# rcontrol.net
KiCad netlist of a schematic drawn in EAGLE
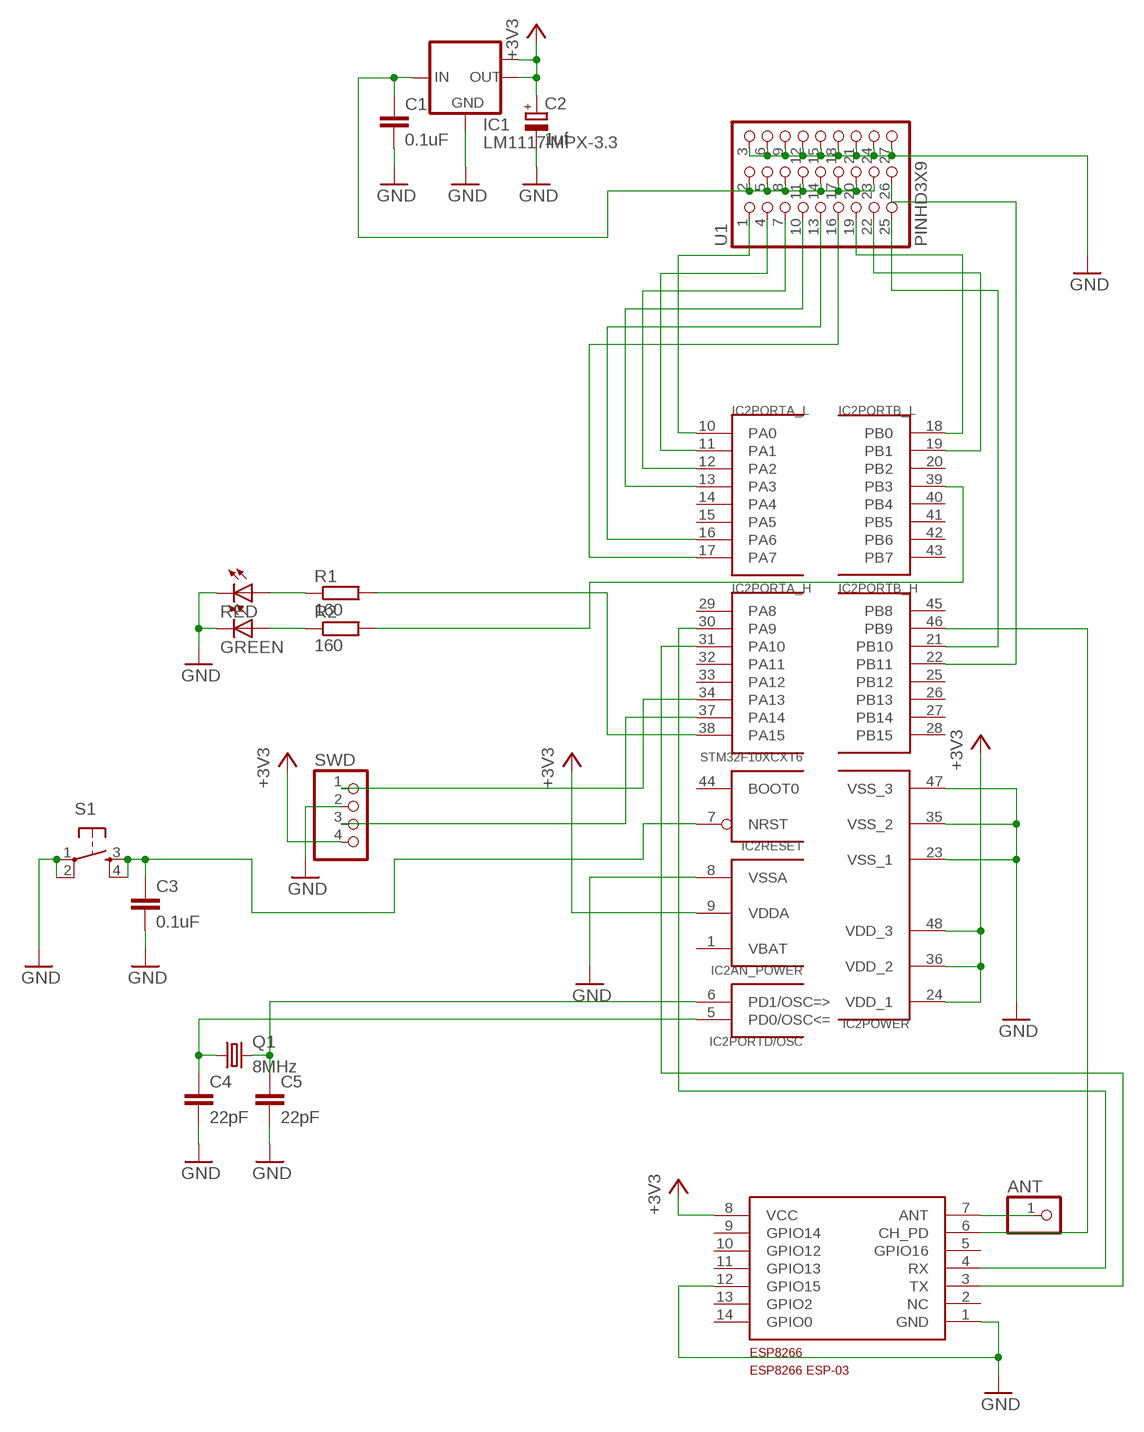
[diagram p0: schematic, sheet 1]

(export (version "E")
  (design (tool "Eeschema 10.0.6"))
  (components
    (comp (ref "ANT")
      (value "PINHD-1X1")
      (footprint "eagle-import:1X01")
      (libsource (lib "eagle-import") (part "PINHD-1X1"))
    )
    (comp (ref "C1")
      (value "0.1uF")
      (footprint "eagle-import:C1206")
      (libsource (lib "eagle-import") (part "C-EUC1206"))
    )
    (comp (ref "C2")
      (value "1uf")
      (footprint "eagle-import:CT3528")
      (libsource (lib "eagle-import") (part "CPOL-EUCT3528"))
    )
    (comp (ref "C3")
      (value "0.1uF")
      (footprint "eagle-import:C0805")
      (libsource (lib "eagle-import") (part "C-EUC0805"))
    )
    (comp (ref "C4")
      (value "22pF")
      (footprint "eagle-import:C0805")
      (libsource (lib "eagle-import") (part "C-EUC0805"))
    )
    (comp (ref "C5")
      (value "22pF")
      (footprint "eagle-import:C0805")
      (libsource (lib "eagle-import") (part "C-EUC0805"))
    )
    (comp (ref "ESP8266")
      (value "ESP8266_ESP-03")
      (footprint "eagle-import:ESP-03")
      (libsource (lib "eagle-import") (part "ESP8266_ESP-03"))
    )
    (comp (ref "GREEN")
      (value "LEDCHIP-LED0805")
      (footprint "eagle-import:CHIP-LED0805")
      (libsource (lib "eagle-import") (part "LEDCHIP-LED0805"))
    )
    (comp (ref "IC1")
      (value "LM1117IMPX-3.3")
      (footprint "eagle-import:SOT223")
      (libsource (lib "eagle-import") (part "LM1117IMPX-3.3"))
    )
    (comp (ref "IC2")
      (value "STM32F10XCXT6")
      (footprint "eagle-import:TQFP48")
      (libsource (lib "eagle-import") (part "STM32F10XCXT6"))
    )
    (comp (ref "Q1")
      (value "8MHz")
      (footprint "eagle-import:HC49U-V")
      (libsource (lib "eagle-import") (part "CRYSTALHC49U-V"))
    )
    (comp (ref "R1")
      (value "160")
      (footprint "eagle-import:R0805")
      (libsource (lib "eagle-import") (part "R-EU_R0805"))
    )
    (comp (ref "R2")
      (value "160")
      (footprint "eagle-import:R0805")
      (libsource (lib "eagle-import") (part "R-EU_R0805"))
    )
    (comp (ref "RED")
      (value "LEDCHIP-LED0805")
      (footprint "eagle-import:CHIP-LED0805")
      (libsource (lib "eagle-import") (part "LEDCHIP-LED0805"))
    )
    (comp (ref "S1")
      (value "TAC_SWITCHSMD")
      (footprint "eagle-import:TACTILE_SWITCH_SMD")
      (libsource (lib "eagle-import") (part "TAC_SWITCHSMD"))
    )
    (comp (ref "SWD")
      (value "PINHD-1X4")
      (footprint "eagle-import:1X04")
      (libsource (lib "eagle-import") (part "PINHD-1X4"))
    )
    (comp (ref "U1")
      (value "PINHD3X9")
      (footprint "eagle-import:3X9")
      (libsource (lib "eagle-import") (part "PINHD3X9"))
    )
  )
  (nets
    (net (code "1") (name "+3V3") (class "Default")
      (node (ref "C2") (pin "+") (pinfunction "+_+") (pintype "passive"))
      (node (ref "ESP8266") (pin "8") (pinfunction "VCC_8") (pintype "bidirectional"))
      (node (ref "IC1") (pin "2") (pinfunction "OUT_2") (pintype "passive"))
      (node (ref "IC1") (pin "TAB") (pinfunction "OUT1_TAB") (pintype "passive"))
      (node (ref "IC2") (pin "24") (pinfunction "VDD_1_24") (pintype "power_in"))
      (node (ref "IC2") (pin "36") (pinfunction "VDD_2_36") (pintype "power_in"))
      (node (ref "IC2") (pin "48") (pinfunction "VDD_3_48") (pintype "power_in"))
      (node (ref "IC2") (pin "9") (pinfunction "VDDA_9") (pintype "power_in"))
      (node (ref "SWD") (pin "4") (pinfunction "4_4") (pintype "passive"))
    )
    (net (code "2") (name "/VBAT") (class "Default")
      (node (ref "IC2") (pin "1") (pinfunction "VBAT_1") (pintype "power_in"))
    )
    (net (code "3") (name "GND") (class "Default")
      (node (ref "C1") (pin "2") (pinfunction "2_2") (pintype "passive"))
      (node (ref "C2") (pin "-") (pinfunction "-_-") (pintype "passive"))
      (node (ref "C3") (pin "2") (pinfunction "2_2") (pintype "passive"))
      (node (ref "C4") (pin "2") (pinfunction "2_2") (pintype "passive"))
      (node (ref "C5") (pin "2") (pinfunction "2_2") (pintype "passive"))
      (node (ref "ESP8266") (pin "1") (pinfunction "GND_1") (pintype "bidirectional"))
      (node (ref "ESP8266") (pin "12") (pinfunction "GPIO15_12") (pintype "bidirectional"))
      (node (ref "GREEN") (pin "C") (pinfunction "C_C") (pintype "passive"))
      (node (ref "IC1") (pin "1") (pinfunction "GND_1") (pintype "input"))
      (node (ref "IC2") (pin "23") (pinfunction "VSS_1_23") (pintype "power_in"))
      (node (ref "IC2") (pin "35") (pinfunction "VSS_2_35") (pintype "power_in"))
      (node (ref "IC2") (pin "47") (pinfunction "VSS_3_47") (pintype "power_in"))
      (node (ref "IC2") (pin "8") (pinfunction "VSSA_8") (pintype "power_in"))
      (node (ref "RED") (pin "C") (pinfunction "C_C") (pintype "passive"))
      (node (ref "S1") (pin "1") (pinfunction "1_1") (pintype "passive"))
      (node (ref "S1") (pin "2") (pinfunction "2_2") (pintype "passive"))
      (node (ref "SWD") (pin "2") (pinfunction "2_2") (pintype "passive"))
      (node (ref "U1") (pin "12") (pinfunction "12_12") (pintype "passive"))
      (node (ref "U1") (pin "15") (pinfunction "15_15") (pintype "passive"))
      (node (ref "U1") (pin "18") (pinfunction "18_18") (pintype "passive"))
      (node (ref "U1") (pin "21") (pinfunction "21_21") (pintype "passive"))
      (node (ref "U1") (pin "24") (pinfunction "24_24") (pintype "passive"))
      (node (ref "U1") (pin "27") (pinfunction "27_27") (pintype "passive"))
      (node (ref "U1") (pin "3") (pinfunction "3_3") (pintype "passive"))
      (node (ref "U1") (pin "6") (pinfunction "6_6") (pintype "passive"))
      (node (ref "U1") (pin "9") (pinfunction "9_9") (pintype "passive"))
    )
    (net (code "4") (name "Net-(ESP8266-ANT)") (class "Default")
      (node (ref "ANT") (pin "1") (pinfunction "1_1") (pintype "passive"))
      (node (ref "ESP8266") (pin "7") (pinfunction "ANT_7") (pintype "bidirectional"))
    )
    (net (code "5") (name "Net-(ESP8266-CH_PD)") (class "Default")
      (node (ref "ESP8266") (pin "6") (pinfunction "CH_PD_6") (pintype "bidirectional"))
      (node (ref "IC2") (pin "46") (pinfunction "PB9_46") (pintype "bidirectional"))
    )
    (net (code "6") (name "Net-(ESP8266-RX)") (class "Default")
      (node (ref "ESP8266") (pin "4") (pinfunction "RX_4") (pintype "bidirectional"))
      (node (ref "IC2") (pin "30") (pinfunction "PA9_30") (pintype "bidirectional"))
    )
    (net (code "7") (name "Net-(ESP8266-TX)") (class "Default")
      (node (ref "ESP8266") (pin "3") (pinfunction "TX_3") (pintype "bidirectional"))
      (node (ref "IC2") (pin "31") (pinfunction "PA10_31") (pintype "bidirectional"))
    )
    (net (code "8") (name "Net-(GREEN-PadA)") (class "Default")
      (node (ref "GREEN") (pin "A") (pinfunction "A_A") (pintype "passive"))
      (node (ref "R2") (pin "1") (pinfunction "1_1") (pintype "passive"))
    )
    (net (code "9") (name "Net-(IC1-IN)") (class "Default")
      (node (ref "C1") (pin "1") (pinfunction "1_1") (pintype "passive"))
      (node (ref "IC1") (pin "3") (pinfunction "IN_3") (pintype "input"))
      (node (ref "U1") (pin "11") (pinfunction "11_11") (pintype "passive"))
      (node (ref "U1") (pin "14") (pinfunction "14_14") (pintype "passive"))
      (node (ref "U1") (pin "17") (pinfunction "17_17") (pintype "passive"))
      (node (ref "U1") (pin "2") (pinfunction "2_2") (pintype "passive"))
      (node (ref "U1") (pin "20") (pinfunction "20_20") (pintype "passive"))
      (node (ref "U1") (pin "23") (pinfunction "23_23") (pintype "passive"))
      (node (ref "U1") (pin "5") (pinfunction "5_5") (pintype "passive"))
      (node (ref "U1") (pin "8") (pinfunction "8_8") (pintype "passive"))
    )
    (net (code "10") (name "Net-(IC2B-PA13)") (class "Default")
      (node (ref "IC2") (pin "34") (pinfunction "PA13_34") (pintype "bidirectional"))
      (node (ref "SWD") (pin "1") (pinfunction "1_1") (pintype "passive"))
    )
    (net (code "11") (name "Net-(IC2B-PA14)") (class "Default")
      (node (ref "IC2") (pin "37") (pinfunction "PA14_37") (pintype "bidirectional"))
      (node (ref "SWD") (pin "3") (pinfunction "3_3") (pintype "passive"))
    )
    (net (code "12") (name "Net-(IC2B-PA15)") (class "Default")
      (node (ref "IC2") (pin "38") (pinfunction "PA15_38") (pintype "bidirectional"))
      (node (ref "R1") (pin "2") (pinfunction "2_2") (pintype "passive"))
    )
    (net (code "13") (name "Net-(IC2C-PA0)") (class "Default")
      (node (ref "IC2") (pin "10") (pinfunction "PA0_10") (pintype "bidirectional"))
      (node (ref "U1") (pin "1") (pinfunction "1_1") (pintype "passive"))
    )
    (net (code "14") (name "Net-(IC2C-PA1)") (class "Default")
      (node (ref "IC2") (pin "11") (pinfunction "PA1_11") (pintype "bidirectional"))
      (node (ref "U1") (pin "4") (pinfunction "4_4") (pintype "passive"))
    )
    (net (code "15") (name "Net-(IC2C-PA2)") (class "Default")
      (node (ref "IC2") (pin "12") (pinfunction "PA2_12") (pintype "bidirectional"))
      (node (ref "U1") (pin "7") (pinfunction "7_7") (pintype "passive"))
    )
    (net (code "16") (name "Net-(IC2C-PA3)") (class "Default")
      (node (ref "IC2") (pin "13") (pinfunction "PA3_13") (pintype "bidirectional"))
      (node (ref "U1") (pin "10") (pinfunction "10_10") (pintype "passive"))
    )
    (net (code "17") (name "Net-(IC2C-PA6)") (class "Default")
      (node (ref "IC2") (pin "16") (pinfunction "PA6_16") (pintype "bidirectional"))
      (node (ref "U1") (pin "13") (pinfunction "13_13") (pintype "passive"))
    )
    (net (code "18") (name "Net-(IC2C-PA7)") (class "Default")
      (node (ref "IC2") (pin "17") (pinfunction "PA7_17") (pintype "bidirectional"))
      (node (ref "U1") (pin "16") (pinfunction "16_16") (pintype "passive"))
    )
    (net (code "19") (name "Net-(IC2D-PB10)") (class "Default")
      (node (ref "IC2") (pin "21") (pinfunction "PB10_21") (pintype "bidirectional"))
      (node (ref "U1") (pin "25") (pinfunction "25_25") (pintype "passive"))
    )
    (net (code "20") (name "Net-(IC2D-PB11)") (class "Default")
      (node (ref "IC2") (pin "22") (pinfunction "PB11_22") (pintype "bidirectional"))
      (node (ref "U1") (pin "26") (pinfunction "26_26") (pintype "passive"))
    )
    (net (code "21") (name "Net-(IC2E-PB0)") (class "Default")
      (node (ref "IC2") (pin "18") (pinfunction "PB0_18") (pintype "bidirectional"))
      (node (ref "U1") (pin "19") (pinfunction "19_19") (pintype "passive"))
    )
    (net (code "22") (name "Net-(IC2E-PB1)") (class "Default")
      (node (ref "IC2") (pin "19") (pinfunction "PB1_19") (pintype "bidirectional"))
      (node (ref "U1") (pin "22") (pinfunction "22_22") (pintype "passive"))
    )
    (net (code "23") (name "Net-(IC2E-PB3)") (class "Default")
      (node (ref "IC2") (pin "39") (pinfunction "PB3_39") (pintype "bidirectional"))
      (node (ref "R2") (pin "2") (pinfunction "2_2") (pintype "passive"))
    )
    (net (code "24") (name "Net-(IC2G-PD0{slash}OSC<=)") (class "Default")
      (node (ref "C4") (pin "1") (pinfunction "1_1") (pintype "passive"))
      (node (ref "IC2") (pin "5") (pinfunction "PD0/OSC<=_5") (pintype "bidirectional"))
      (node (ref "Q1") (pin "1") (pinfunction "1_1") (pintype "passive"))
    )
    (net (code "25") (name "Net-(IC2G-PD1{slash}OSC=>)") (class "Default")
      (node (ref "C5") (pin "1") (pinfunction "1_1") (pintype "passive"))
      (node (ref "IC2") (pin "6") (pinfunction "PD1/OSC=>_6") (pintype "bidirectional"))
      (node (ref "Q1") (pin "2") (pinfunction "2_2") (pintype "passive"))
    )
    (net (code "26") (name "Net-(IC2I-NRST)") (class "Default")
      (node (ref "C3") (pin "1") (pinfunction "1_1") (pintype "passive"))
      (node (ref "IC2") (pin "7") (pinfunction "NRST_7") (pintype "input"))
      (node (ref "S1") (pin "3") (pinfunction "3_3") (pintype "passive"))
      (node (ref "S1") (pin "4") (pinfunction "4_4") (pintype "passive"))
    )
    (net (code "27") (name "Net-(R1-Pad1)") (class "Default")
      (node (ref "R1") (pin "1") (pinfunction "1_1") (pintype "passive"))
      (node (ref "RED") (pin "A") (pinfunction "A_A") (pintype "passive"))
    )
    (net (code "28") (name "unconnected-(ESP8266-GPIO0-Pad14)") (class "Default")
      (node (ref "ESP8266") (pin "14") (pinfunction "GPIO0_14") (pintype "bidirectional"))
    )
    (net (code "29") (name "unconnected-(ESP8266-GPIO2-Pad13)") (class "Default")
      (node (ref "ESP8266") (pin "13") (pinfunction "GPIO2_13") (pintype "bidirectional"))
    )
    (net (code "30") (name "unconnected-(ESP8266-GPIO12-Pad10)") (class "Default")
      (node (ref "ESP8266") (pin "10") (pinfunction "GPIO12_10") (pintype "bidirectional"))
    )
    (net (code "31") (name "unconnected-(ESP8266-GPIO13-Pad11)") (class "Default")
      (node (ref "ESP8266") (pin "11") (pinfunction "GPIO13_11") (pintype "bidirectional"))
    )
    (net (code "32") (name "unconnected-(ESP8266-GPIO14-Pad9)") (class "Default")
      (node (ref "ESP8266") (pin "9") (pinfunction "GPIO14_9") (pintype "bidirectional"))
    )
    (net (code "33") (name "unconnected-(ESP8266-GPIO16-Pad5)") (class "Default")
      (node (ref "ESP8266") (pin "5") (pinfunction "GPIO16_5") (pintype "bidirectional"))
    )
    (net (code "34") (name "unconnected-(ESP8266-NC-Pad2)") (class "Default")
      (node (ref "ESP8266") (pin "2") (pinfunction "NC_2") (pintype "bidirectional"))
    )
    (net (code "35") (name "unconnected-(IC2B-PA8-Pad29)") (class "Default")
      (node (ref "IC2") (pin "29") (pinfunction "PA8_29") (pintype "bidirectional"))
    )
    (net (code "36") (name "unconnected-(IC2B-PA11-Pad32)") (class "Default")
      (node (ref "IC2") (pin "32") (pinfunction "PA11_32") (pintype "bidirectional"))
    )
    (net (code "37") (name "unconnected-(IC2B-PA12-Pad33)") (class "Default")
      (node (ref "IC2") (pin "33") (pinfunction "PA12_33") (pintype "bidirectional"))
    )
    (net (code "38") (name "unconnected-(IC2C-PA4-Pad14)") (class "Default")
      (node (ref "IC2") (pin "14") (pinfunction "PA4_14") (pintype "bidirectional"))
    )
    (net (code "39") (name "unconnected-(IC2C-PA5-Pad15)") (class "Default")
      (node (ref "IC2") (pin "15") (pinfunction "PA5_15") (pintype "bidirectional"))
    )
    (net (code "40") (name "unconnected-(IC2D-PB8-Pad45)") (class "Default")
      (node (ref "IC2") (pin "45") (pinfunction "PB8_45") (pintype "bidirectional"))
    )
    (net (code "41") (name "unconnected-(IC2D-PB12-Pad25)") (class "Default")
      (node (ref "IC2") (pin "25") (pinfunction "PB12_25") (pintype "bidirectional"))
    )
    (net (code "42") (name "unconnected-(IC2D-PB13-Pad26)") (class "Default")
      (node (ref "IC2") (pin "26") (pinfunction "PB13_26") (pintype "bidirectional"))
    )
    (net (code "43") (name "unconnected-(IC2D-PB14-Pad27)") (class "Default")
      (node (ref "IC2") (pin "27") (pinfunction "PB14_27") (pintype "bidirectional"))
    )
    (net (code "44") (name "unconnected-(IC2D-PB15-Pad28)") (class "Default")
      (node (ref "IC2") (pin "28") (pinfunction "PB15_28") (pintype "bidirectional"))
    )
    (net (code "45") (name "unconnected-(IC2E-PB2-Pad20)") (class "Default")
      (node (ref "IC2") (pin "20") (pinfunction "PB2_20") (pintype "bidirectional"))
    )
    (net (code "46") (name "unconnected-(IC2E-PB4-Pad40)") (class "Default")
      (node (ref "IC2") (pin "40") (pinfunction "PB4_40") (pintype "bidirectional"))
    )
    (net (code "47") (name "unconnected-(IC2E-PB5-Pad41)") (class "Default")
      (node (ref "IC2") (pin "41") (pinfunction "PB5_41") (pintype "bidirectional"))
    )
    (net (code "48") (name "unconnected-(IC2E-PB6-Pad42)") (class "Default")
      (node (ref "IC2") (pin "42") (pinfunction "PB6_42") (pintype "bidirectional"))
    )
    (net (code "49") (name "unconnected-(IC2E-PB7-Pad43)") (class "Default")
      (node (ref "IC2") (pin "43") (pinfunction "PB7_43") (pintype "bidirectional"))
    )
    (net (code "50") (name "unconnected-(IC2I-BOOT0-Pad44)") (class "Default")
      (node (ref "IC2") (pin "44") (pinfunction "BOOT0_44") (pintype "input"))
    )
  )
)
